# rc.net
KiCad netlist of a schematic drawn in EAGLE
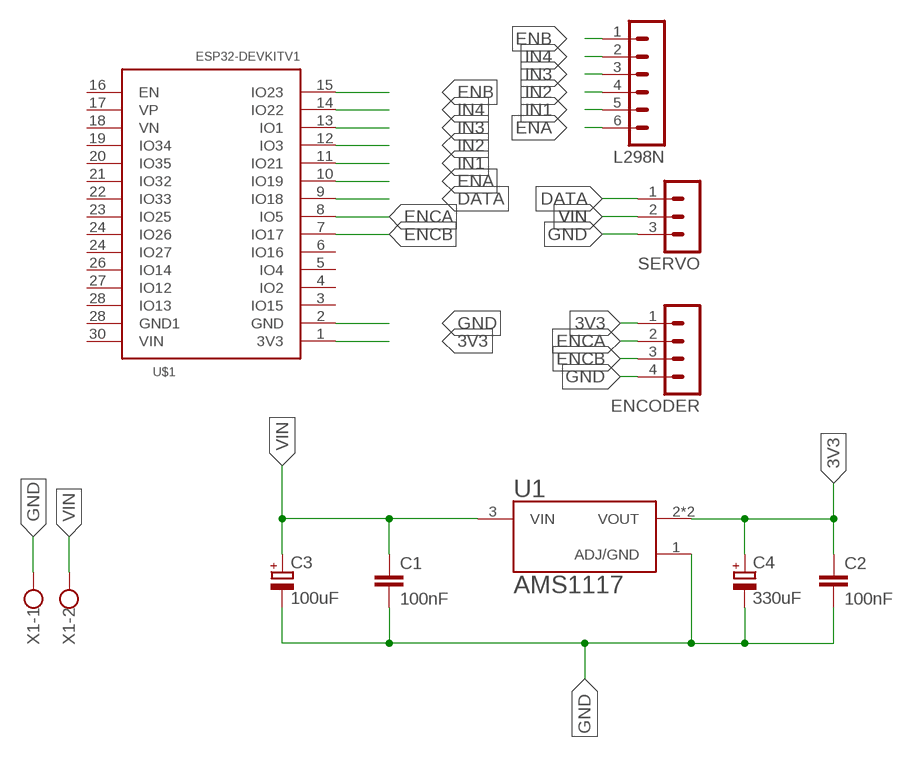
[diagram p0: schematic, sheet 1]

(export (version "E")
  (design (tool "Eeschema 10.0.6"))
  (components
    (comp (ref "C1")
      (value "100nF")
      (footprint "eagle-import:C0805")
      (libsource (lib "eagle-import") (part "C-EUC0805"))
    )
    (comp (ref "C2")
      (value "100nF")
      (footprint "eagle-import:C0805")
      (libsource (lib "eagle-import") (part "C-EUC0805"))
    )
    (comp (ref "C3")
      (value "100uF")
      (footprint "eagle-import:CT6032")
      (libsource (lib "eagle-import") (part "CPOL-EUCT6032"))
    )
    (comp (ref "C4")
      (value "330uF")
      (footprint "eagle-import:CT6032")
      (libsource (lib "eagle-import") (part "CPOL-EUCT6032"))
    )
    (comp (ref "ENCODER")
      (value "MA04-1")
      (footprint "eagle-import:MA04-1")
      (libsource (lib "eagle-import") (part "MA04-1"))
    )
    (comp (ref "L298N")
      (value "MA06-1")
      (footprint "eagle-import:MA06-1")
      (libsource (lib "eagle-import") (part "MA06-1"))
    )
    (comp (ref "SERVO")
      (value "MA03-1")
      (footprint "eagle-import:MA03-1")
      (libsource (lib "eagle-import") (part "MA03-1"))
    )
    (comp (ref "U$1")
      (value "ESP32DEVKITV1")
      (footprint "eagle-import:ESP32-DEVKITV1")
      (libsource (lib "eagle-import") (part "ESP32DEVKITV1"))
    )
    (comp (ref "U1")
      (value "AMS1117")
      (footprint "eagle-import:SOT229P700X180-4N")
      (fields (field (name "MF") "Advanced Monolithic Systems"))
      (libsource (lib "eagle-import") (part "AMS1117"))
    )
    (comp (ref "X1")
      (value "W237-102")
      (footprint "eagle-import:W237-102")
      (fields (field (name "MPN") "237-102"))
      (libsource (lib "eagle-import") (part "W237-102"))
    )
  )
  (nets
    (net (code "1") (name "3V3") (class "Default")
      (node (ref "C2") (pin "1") (pinfunction "1_1") (pintype "passive"))
      (node (ref "C4") (pin "+") (pinfunction "+_+") (pintype "passive"))
      (node (ref "ENCODER") (pin "1") (pinfunction "1_1") (pintype "passive"))
      (node (ref "U$1") (pin "1") (pinfunction "3V3_1") (pintype "bidirectional"))
      (node (ref "U1") (pin "2") (pinfunction "VOUT_2") (pintype "output"))
      (node (ref "U1") (pin "4") (pinfunction "VOUT_4") (pintype "output"))
    )
    (net (code "2") (name "DATA") (class "Default")
      (node (ref "SERVO") (pin "1") (pinfunction "1_1") (pintype "passive"))
      (node (ref "U$1") (pin "9") (pinfunction "IO18_9") (pintype "bidirectional"))
    )
    (net (code "3") (name "ENA") (class "Default")
      (node (ref "L298N") (pin "6") (pinfunction "6_6") (pintype "passive"))
      (node (ref "U$1") (pin "10") (pinfunction "IO19_10") (pintype "bidirectional"))
    )
    (net (code "4") (name "ENB") (class "Default")
      (node (ref "L298N") (pin "1") (pinfunction "1_1") (pintype "passive"))
      (node (ref "U$1") (pin "15") (pinfunction "IO23_15") (pintype "bidirectional"))
    )
    (net (code "5") (name "ENCA") (class "Default")
      (node (ref "ENCODER") (pin "2") (pinfunction "2_2") (pintype "passive"))
      (node (ref "U$1") (pin "8") (pinfunction "IO5_8") (pintype "bidirectional"))
    )
    (net (code "6") (name "ENCB") (class "Default")
      (node (ref "ENCODER") (pin "3") (pinfunction "3_3") (pintype "passive"))
      (node (ref "U$1") (pin "7") (pinfunction "IO17_7") (pintype "bidirectional"))
    )
    (net (code "7") (name "GND") (class "Default")
      (node (ref "C1") (pin "2") (pinfunction "2_2") (pintype "passive"))
      (node (ref "C2") (pin "2") (pinfunction "2_2") (pintype "passive"))
      (node (ref "C3") (pin "-") (pinfunction "-_-") (pintype "passive"))
      (node (ref "C4") (pin "-") (pinfunction "-_-") (pintype "passive"))
      (node (ref "ENCODER") (pin "4") (pinfunction "4_4") (pintype "passive"))
      (node (ref "SERVO") (pin "3") (pinfunction "3_3") (pintype "passive"))
      (node (ref "U$1") (pin "2") (pinfunction "GND_2") (pintype "bidirectional"))
      (node (ref "U1") (pin "1") (pinfunction "ADJ/GND_1") (pintype "power_in"))
      (node (ref "X1") (pin "1") (pinfunction "KL_1") (pintype "passive"))
    )
    (net (code "8") (name "IN1") (class "Default")
      (node (ref "L298N") (pin "5") (pinfunction "5_5") (pintype "passive"))
      (node (ref "U$1") (pin "11") (pinfunction "IO21_11") (pintype "bidirectional"))
    )
    (net (code "9") (name "IN2") (class "Default")
      (node (ref "L298N") (pin "4") (pinfunction "4_4") (pintype "passive"))
      (node (ref "U$1") (pin "12") (pinfunction "IO3_12") (pintype "bidirectional"))
    )
    (net (code "10") (name "IN3") (class "Default")
      (node (ref "L298N") (pin "3") (pinfunction "3_3") (pintype "passive"))
      (node (ref "U$1") (pin "13") (pinfunction "IO1_13") (pintype "bidirectional"))
    )
    (net (code "11") (name "IN4") (class "Default")
      (node (ref "L298N") (pin "2") (pinfunction "2_2") (pintype "passive"))
      (node (ref "U$1") (pin "14") (pinfunction "IO22_14") (pintype "bidirectional"))
    )
    (net (code "12") (name "VIN") (class "Default")
      (node (ref "C1") (pin "1") (pinfunction "1_1") (pintype "passive"))
      (node (ref "C3") (pin "+") (pinfunction "+_+") (pintype "passive"))
      (node (ref "SERVO") (pin "2") (pinfunction "2_2") (pintype "passive"))
      (node (ref "U1") (pin "3") (pinfunction "VIN_3") (pintype "input"))
      (node (ref "X1") (pin "2") (pinfunction "KL_2") (pintype "passive"))
    )
    (net (code "13") (name "unconnected-(U$1-EN-Pad16)") (class "Default")
      (node (ref "U$1") (pin "16") (pinfunction "EN_16") (pintype "bidirectional"))
    )
    (net (code "14") (name "unconnected-(U$1-GND1-Pad28)") (class "Default")
      (node (ref "U$1") (pin "28") (pinfunction "GND1_28") (pintype "bidirectional"))
    )
    (net (code "15") (name "unconnected-(U$1-IO2-Pad4)") (class "Default")
      (node (ref "U$1") (pin "4") (pinfunction "IO2_4") (pintype "bidirectional"))
    )
    (net (code "16") (name "unconnected-(U$1-IO4-Pad5)") (class "Default")
      (node (ref "U$1") (pin "5") (pinfunction "IO4_5") (pintype "bidirectional"))
    )
    (net (code "17") (name "unconnected-(U$1-IO12-Pad27)") (class "Default")
      (node (ref "U$1") (pin "27") (pinfunction "IO12_27") (pintype "bidirectional"))
    )
    (net (code "18") (name "unconnected-(U$1-IO13-Pad28)") (class "Default")
      (node (ref "U$1") (pin "28") (pinfunction "IO13_28") (pintype "bidirectional"))
    )
    (net (code "19") (name "unconnected-(U$1-IO14-Pad26)") (class "Default")
      (node (ref "U$1") (pin "26") (pinfunction "IO14_26") (pintype "bidirectional"))
    )
    (net (code "20") (name "unconnected-(U$1-IO15-Pad3)") (class "Default")
      (node (ref "U$1") (pin "3") (pinfunction "IO15_3") (pintype "bidirectional"))
    )
    (net (code "21") (name "unconnected-(U$1-IO16-Pad6)") (class "Default")
      (node (ref "U$1") (pin "6") (pinfunction "IO16_6") (pintype "bidirectional"))
    )
    (net (code "22") (name "unconnected-(U$1-IO25-Pad23)") (class "Default")
      (node (ref "U$1") (pin "23") (pinfunction "IO25_23") (pintype "bidirectional"))
    )
    (net (code "23") (name "unconnected-(U$1-IO26-Pad24)") (class "Default")
      (node (ref "U$1") (pin "24") (pinfunction "IO26_24") (pintype "bidirectional"))
    )
    (net (code "24") (name "unconnected-(U$1-IO27-Pad24)") (class "Default")
      (node (ref "U$1") (pin "24") (pinfunction "IO27_24") (pintype "bidirectional"))
    )
    (net (code "25") (name "unconnected-(U$1-IO32-Pad21)") (class "Default")
      (node (ref "U$1") (pin "21") (pinfunction "IO32_21") (pintype "bidirectional"))
    )
    (net (code "26") (name "unconnected-(U$1-IO33-Pad22)") (class "Default")
      (node (ref "U$1") (pin "22") (pinfunction "IO33_22") (pintype "bidirectional"))
    )
    (net (code "27") (name "unconnected-(U$1-IO34-Pad19)") (class "Default")
      (node (ref "U$1") (pin "19") (pinfunction "IO34_19") (pintype "bidirectional"))
    )
    (net (code "28") (name "unconnected-(U$1-IO35-Pad20)") (class "Default")
      (node (ref "U$1") (pin "20") (pinfunction "IO35_20") (pintype "bidirectional"))
    )
    (net (code "29") (name "unconnected-(U$1-VIN-Pad30)") (class "Default")
      (node (ref "U$1") (pin "30") (pinfunction "VIN_30") (pintype "bidirectional"))
    )
    (net (code "30") (name "unconnected-(U$1-VN-Pad18)") (class "Default")
      (node (ref "U$1") (pin "18") (pinfunction "VN_18") (pintype "bidirectional"))
    )
    (net (code "31") (name "unconnected-(U$1-VP-Pad17)") (class "Default")
      (node (ref "U$1") (pin "17") (pinfunction "VP_17") (pintype "bidirectional"))
    )
  )
)
